# TEMPLATE_Circuit.net
KiCad netlist of a schematic drawn in Altium Designer
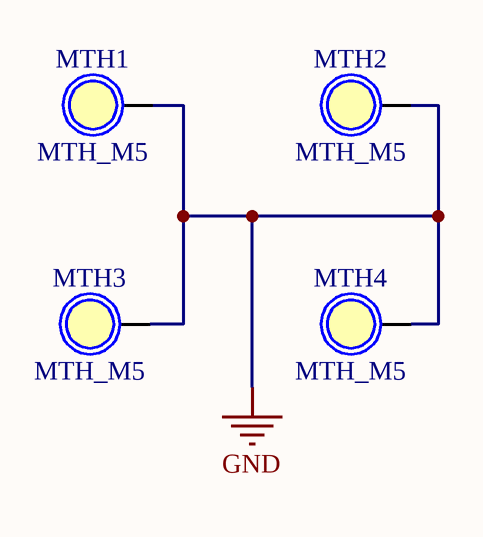
[diagram p0: TEMPLATE_Circuit.SchDoc]

(export (version "E")
  (design (tool "Eeschema 10.0.6"))
  (components
    (comp (ref "MTH1")
      (value "MTH_M5")
      (footprint "MTH_M5")
      (description "MTH - MOUNTING HOLE 5MM PLATED - 5MM")
      (fields (field (name "SOURCE") "CEGEP_SHERBROOKE_TGE_LIBRARY.SchLib"))
      (libsource (lib "Cegep de Sherbrooke") (part "MTH_M3.5_PLATED"))
    )
    (comp (ref "MTH2")
      (value "MTH_M5")
      (footprint "MTH_M5")
      (description "MTH - MOUNTING HOLE 5MM PLATED - 5MM")
      (fields (field (name "SOURCE") "CEGEP_SHERBROOKE_TGE_LIBRARY.SchLib"))
      (libsource (lib "Cegep de Sherbrooke") (part "MTH_M3.5_PLATED"))
    )
    (comp (ref "MTH3")
      (value "MTH_M5")
      (footprint "MTH_M5")
      (description "MTH - MOUNTING HOLE 5MM PLATED - 5MM")
      (fields (field (name "SOURCE") "CEGEP_SHERBROOKE_TGE_LIBRARY.SchLib"))
      (libsource (lib "Cegep de Sherbrooke") (part "MTH_M3.5_PLATED"))
    )
    (comp (ref "MTH4")
      (value "MTH_M5")
      (footprint "MTH_M5")
      (description "MTH - MOUNTING HOLE 5MM PLATED - 5MM")
      (fields (field (name "SOURCE") "CEGEP_SHERBROOKE_TGE_LIBRARY.SchLib"))
      (libsource (lib "Cegep de Sherbrooke") (part "MTH_M3.5_PLATED"))
    )
  )
  (nets
    (net (code "1") (name "GND") (class "Default")
      (node (ref "MTH1") (pin "1") (pinfunction "1_1") (pintype "passive"))
      (node (ref "MTH2") (pin "1") (pinfunction "1_1") (pintype "passive"))
      (node (ref "MTH3") (pin "1") (pinfunction "1_1") (pintype "passive"))
      (node (ref "MTH4") (pin "1") (pinfunction "1_1") (pintype "passive"))
    )
  )
)
